# Carte-Principale.net
KiCad netlist of a schematic drawn in EAGLE
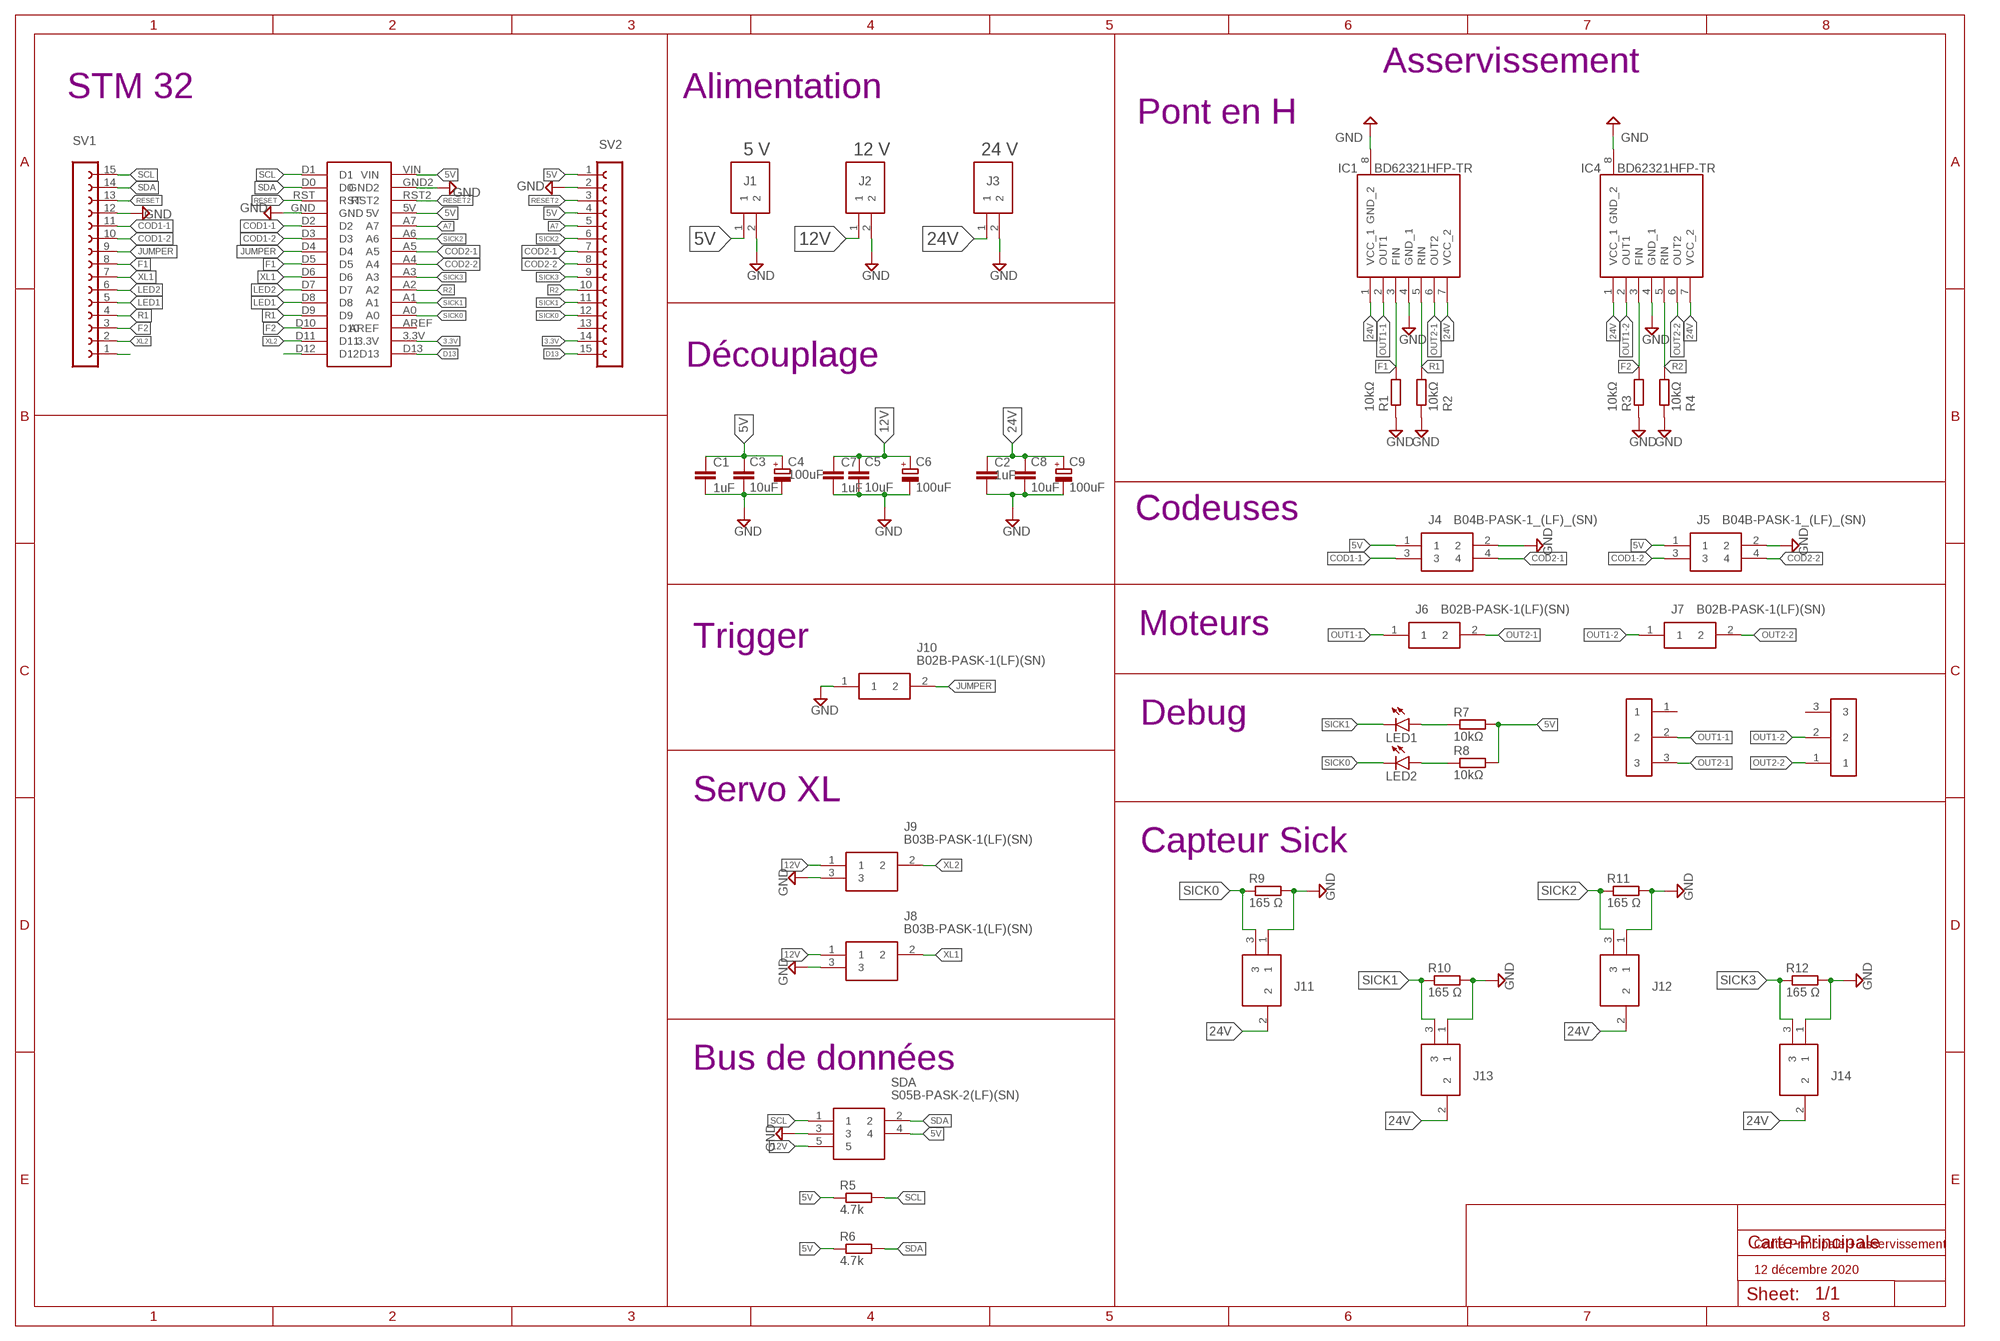
[diagram p0: schematic, sheet 1]

(export (version "E")
  (design (tool "Eeschema 10.0.6"))
  (components
    (comp (ref "C1")
      (value "1uF")
      (footprint "eagle-import:C0805")
      (libsource (lib "eagle-import") (part "C-EUC0805"))
    )
    (comp (ref "C2")
      (value "1uF")
      (footprint "eagle-import:C0805")
      (libsource (lib "eagle-import") (part "C-EUC0805"))
    )
    (comp (ref "C3")
      (value "10uF")
      (footprint "eagle-import:C0805")
      (libsource (lib "eagle-import") (part "C-EUC0805"))
    )
    (comp (ref "C4")
      (value "100uF")
      (footprint "eagle-import:153CLV-0605")
      (libsource (lib "eagle-import") (part "CPOL-EU153CLV-0605"))
    )
    (comp (ref "C5")
      (value "10uF")
      (footprint "eagle-import:C0805")
      (libsource (lib "eagle-import") (part "C-EUC0805"))
    )
    (comp (ref "C6")
      (value "100uF")
      (footprint "eagle-import:153CLV-0605")
      (libsource (lib "eagle-import") (part "CPOL-EU153CLV-0605"))
    )
    (comp (ref "C7")
      (value "1uF")
      (footprint "eagle-import:C0805")
      (libsource (lib "eagle-import") (part "C-EUC0805"))
    )
    (comp (ref "C8")
      (value "10uF")
      (footprint "eagle-import:C0805")
      (libsource (lib "eagle-import") (part "C-EUC0805"))
    )
    (comp (ref "C9")
      (value "100uF")
      (footprint "eagle-import:153CLV-0605")
      (libsource (lib "eagle-import") (part "CPOL-EU153CLV-0605"))
    )
    (comp (ref "IC1")
      (value "BD62321HFP-TR")
      (footprint "eagle-import:HRP7")
      (fields (field (name "MOUSER_PART_NUMBER") "755-BD62321HFP-TR"))
      (libsource (lib "eagle-import") (part "BD62321HFP-TR"))
    )
    (comp (ref "IC4")
      (value "BD62321HFP-TR")
      (footprint "eagle-import:HRP7")
      (fields (field (name "MOUSER_PART_NUMBER") "755-BD62321HFP-TR"))
      (libsource (lib "eagle-import") (part "BD62321HFP-TR"))
    )
    (comp (ref "J1")
      (value "B2P-VH(LF)(SN)")
      (footprint "eagle-import:SHDR2W114P0X396_1X2_786X850X94")
      (fields (field (name "RS_PART_NUMBER") "8201147P"))
      (libsource (lib "eagle-import") (part "B2P-VH(LF)(SN)"))
    )
    (comp (ref "J2")
      (value "B2P-VH(LF)(SN)")
      (footprint "eagle-import:SHDR2W114P0X396_1X2_786X850X94")
      (fields (field (name "RS_PART_NUMBER") "8201147P"))
      (libsource (lib "eagle-import") (part "B2P-VH(LF)(SN)"))
    )
    (comp (ref "J3")
      (value "B2P-VH(LF)(SN)")
      (footprint "eagle-import:SHDR2W114P0X396_1X2_786X850X94")
      (fields (field (name "RS_PART_NUMBER") "8201147P"))
      (libsource (lib "eagle-import") (part "B2P-VH(LF)(SN)"))
    )
    (comp (ref "J4")
      (value "B04B-PASK-1_(LF)_(SN)")
      (footprint "eagle-import:B04B-PASK-1")
      (fields
        (field (name "MANUFACTURER_PART_NUMBER") "B04B-PASK-1 (LF) (SN)")
        (field (name "RS_PART_NUMBER") "5128608P")
      )
      (libsource (lib "eagle-import") (part "B04B-PASK-1_(LF)_(SN)"))
    )
    (comp (ref "J5")
      (value "B04B-PASK-1_(LF)_(SN)")
      (footprint "eagle-import:B04B-PASK-1")
      (fields
        (field (name "MANUFACTURER_PART_NUMBER") "B04B-PASK-1 (LF) (SN)")
        (field (name "RS_PART_NUMBER") "5128608P")
      )
      (libsource (lib "eagle-import") (part "B04B-PASK-1_(LF)_(SN)"))
    )
    (comp (ref "J6")
      (value "B02B-PASK-1(LF)(SN)")
      (footprint "eagle-import:B02BPASK1LFSN")
      (libsource (lib "eagle-import") (part "B02B-PASK-1(LF)(SN)"))
    )
    (comp (ref "J7")
      (value "B02B-PASK-1(LF)(SN)")
      (footprint "eagle-import:B02BPASK1LFSN")
      (libsource (lib "eagle-import") (part "B02B-PASK-1(LF)(SN)"))
    )
    (comp (ref "J8")
      (value "B03B-PASK-1(LF)(SN)")
      (footprint "eagle-import:B03BPASK1LFSN")
      (libsource (lib "eagle-import") (part "B03B-PASK-1(LF)(SN)"))
    )
    (comp (ref "J9")
      (value "B03B-PASK-1(LF)(SN)")
      (footprint "eagle-import:B03BPASK1LFSN")
      (libsource (lib "eagle-import") (part "B03B-PASK-1(LF)(SN)"))
    )
    (comp (ref "J10")
      (value "B02B-PASK-1(LF)(SN)")
      (footprint "eagle-import:B02BPASK1LFSN")
      (libsource (lib "eagle-import") (part "B02B-PASK-1(LF)(SN)"))
    )
    (comp (ref "J11")
      (value "B03B-PASK-1(LF)(SN)")
      (footprint "eagle-import:B03BPASK1LFSN")
      (libsource (lib "eagle-import") (part "B03B-PASK-1(LF)(SN)"))
    )
    (comp (ref "J12")
      (value "B03B-PASK-1(LF)(SN)")
      (footprint "eagle-import:B03BPASK1LFSN")
      (libsource (lib "eagle-import") (part "B03B-PASK-1(LF)(SN)"))
    )
    (comp (ref "J13")
      (value "B03B-PASK-1(LF)(SN)")
      (footprint "eagle-import:B03BPASK1LFSN")
      (libsource (lib "eagle-import") (part "B03B-PASK-1(LF)(SN)"))
    )
    (comp (ref "J14")
      (value "B03B-PASK-1(LF)(SN)")
      (footprint "eagle-import:B03BPASK1LFSN")
      (libsource (lib "eagle-import") (part "B03B-PASK-1(LF)(SN)"))
    )
    (comp (ref "LED1")
      (value "LEDCHIP-LED0805")
      (footprint "eagle-import:CHIP-LED0805")
      (libsource (lib "eagle-import") (part "LEDCHIP-LED0805"))
    )
    (comp (ref "LED2")
      (value "LEDCHIP-LED0805")
      (footprint "eagle-import:CHIP-LED0805")
      (libsource (lib "eagle-import") (part "LEDCHIP-LED0805"))
    )
    (comp (ref "R1")
      (value "10kΩ")
      (footprint "eagle-import:R0805")
      (libsource (lib "eagle-import") (part "R-EU_R0805"))
    )
    (comp (ref "R2")
      (value "10kΩ")
      (footprint "eagle-import:R0805")
      (libsource (lib "eagle-import") (part "R-EU_R0805"))
    )
    (comp (ref "R3")
      (value "10kΩ")
      (footprint "eagle-import:R0805")
      (libsource (lib "eagle-import") (part "R-EU_R0805"))
    )
    (comp (ref "R4")
      (value "10kΩ")
      (footprint "eagle-import:R0805")
      (libsource (lib "eagle-import") (part "R-EU_R0805"))
    )
    (comp (ref "R5")
      (value "4.7k")
      (footprint "eagle-import:R01005")
      (libsource (lib "eagle-import") (part "R-EU_01005"))
    )
    (comp (ref "R6")
      (value "4.7k")
      (footprint "eagle-import:R01005")
      (libsource (lib "eagle-import") (part "R-EU_01005"))
    )
    (comp (ref "R7")
      (value "10kΩ")
      (footprint "eagle-import:R0805")
      (libsource (lib "eagle-import") (part "R-EU_R0805"))
    )
    (comp (ref "R8")
      (value "10kΩ")
      (footprint "eagle-import:R0805")
      (libsource (lib "eagle-import") (part "R-EU_R0805"))
    )
    (comp (ref "R9")
      (value "165 Ω")
      (footprint "eagle-import:R0805")
      (libsource (lib "eagle-import") (part "R-EU_R0805"))
    )
    (comp (ref "R10")
      (value "165 Ω")
      (footprint "eagle-import:R0805")
      (libsource (lib "eagle-import") (part "R-EU_R0805"))
    )
    (comp (ref "R11")
      (value "165 Ω")
      (footprint "eagle-import:R0805")
      (libsource (lib "eagle-import") (part "R-EU_R0805"))
    )
    (comp (ref "R12")
      (value "165 Ω")
      (footprint "eagle-import:R0805")
      (libsource (lib "eagle-import") (part "R-EU_R0805"))
    )
    (comp (ref "SDA")
      (value "S05B-PASK-2(LF)(SN)")
      (footprint "eagle-import:S05B-PASK-2(LF)(SN)")
      (libsource (lib "eagle-import") (part "S05B-PASK-2(LF)(SN)"))
    )
    (comp (ref "SV1")
      (value "FE15-1")
      (footprint "eagle-import:FE15")
      (libsource (lib "eagle-import") (part "FE15-1"))
    )
    (comp (ref "SV2")
      (value "FE15-1")
      (footprint "eagle-import:FE15")
      (libsource (lib "eagle-import") (part "FE15-1"))
    )
    (comp (ref "U$1")
      (value "STM32-L432KC")
      (footprint "eagle-import:STM32-L432KC")
      (libsource (lib "eagle-import") (part "STM32-L432KC"))
    )
    (comp (ref "U$2")
      (value "HEADER3PIN")
      (footprint "eagle-import:HEADER3PINFOOTPRINT")
      (libsource (lib "eagle-import") (part "HEADER3PIN"))
    )
    (comp (ref "U$3")
      (value "HEADER3PIN")
      (footprint "eagle-import:HEADER3PINFOOTPRINT")
      (libsource (lib "eagle-import") (part "HEADER3PIN"))
    )
  )
  (nets
    (net (code "1") (name "3.3V") (class "Default")
      (node (ref "SV2") (pin "14") (pinfunction "14_14") (pintype "passive"))
      (node (ref "U$1") (pin "3.3V") (pinfunction "3.3V_3.3V") (pintype "bidirectional"))
    )
    (net (code "2") (name "5V") (class "Default")
      (node (ref "C1") (pin "1") (pinfunction "1_1") (pintype "passive"))
      (node (ref "C3") (pin "1") (pinfunction "1_1") (pintype "passive"))
      (node (ref "C4") (pin "+") (pinfunction "+_+") (pintype "passive"))
      (node (ref "J1") (pin "1") (pinfunction "1_1") (pintype "bidirectional"))
      (node (ref "J4") (pin "1") (pinfunction "1_1") (pintype "bidirectional"))
      (node (ref "J5") (pin "1") (pinfunction "1_1") (pintype "bidirectional"))
      (node (ref "R5") (pin "1") (pinfunction "1_1") (pintype "passive"))
      (node (ref "R6") (pin "1") (pinfunction "1_1") (pintype "passive"))
      (node (ref "R7") (pin "2") (pinfunction "2_2") (pintype "passive"))
      (node (ref "R8") (pin "2") (pinfunction "2_2") (pintype "passive"))
      (node (ref "SDA") (pin "4") (pinfunction "4_4") (pintype "bidirectional"))
      (node (ref "SV2") (pin "1") (pinfunction "1_1") (pintype "passive"))
      (node (ref "SV2") (pin "4") (pinfunction "4_4") (pintype "passive"))
      (node (ref "U$1") (pin "5V") (pinfunction "5V_5V") (pintype "bidirectional"))
      (node (ref "U$1") (pin "VIN") (pinfunction "VIN_VIN") (pintype "bidirectional"))
    )
    (net (code "3") (name "12V") (class "Default")
      (node (ref "C5") (pin "1") (pinfunction "1_1") (pintype "passive"))
      (node (ref "C6") (pin "+") (pinfunction "+_+") (pintype "passive"))
      (node (ref "C7") (pin "1") (pinfunction "1_1") (pintype "passive"))
      (node (ref "J2") (pin "1") (pinfunction "1_1") (pintype "bidirectional"))
      (node (ref "J8") (pin "1") (pinfunction "1_1") (pintype "bidirectional"))
      (node (ref "J9") (pin "1") (pinfunction "1_1") (pintype "bidirectional"))
      (node (ref "SDA") (pin "5") (pinfunction "5_5") (pintype "bidirectional"))
    )
    (net (code "4") (name "24V") (class "Default")
      (node (ref "C2") (pin "1") (pinfunction "1_1") (pintype "passive"))
      (node (ref "C8") (pin "1") (pinfunction "1_1") (pintype "passive"))
      (node (ref "C9") (pin "+") (pinfunction "+_+") (pintype "passive"))
      (node (ref "IC1") (pin "1") (pinfunction "VCC_1_1") (pintype "bidirectional"))
      (node (ref "IC1") (pin "7") (pinfunction "VCC_2_7") (pintype "bidirectional"))
      (node (ref "IC4") (pin "1") (pinfunction "VCC_1_1") (pintype "bidirectional"))
      (node (ref "IC4") (pin "7") (pinfunction "VCC_2_7") (pintype "bidirectional"))
      (node (ref "J11") (pin "2") (pinfunction "2_2") (pintype "bidirectional"))
      (node (ref "J12") (pin "2") (pinfunction "2_2") (pintype "bidirectional"))
      (node (ref "J13") (pin "2") (pinfunction "2_2") (pintype "bidirectional"))
      (node (ref "J14") (pin "2") (pinfunction "2_2") (pintype "bidirectional"))
      (node (ref "J3") (pin "1") (pinfunction "1_1") (pintype "bidirectional"))
    )
    (net (code "5") (name "A7") (class "Default")
      (node (ref "SV2") (pin "5") (pinfunction "5_5") (pintype "passive"))
      (node (ref "U$1") (pin "A7") (pinfunction "A7_A7") (pintype "bidirectional"))
    )
    (net (code "6") (name "COD1-1") (class "Default")
      (node (ref "J4") (pin "3") (pinfunction "3_3") (pintype "bidirectional"))
      (node (ref "SV1") (pin "11") (pinfunction "11_11") (pintype "passive"))
      (node (ref "U$1") (pin "D2") (pinfunction "D2_D2") (pintype "bidirectional"))
    )
    (net (code "7") (name "COD1-2") (class "Default")
      (node (ref "J5") (pin "3") (pinfunction "3_3") (pintype "bidirectional"))
      (node (ref "SV1") (pin "10") (pinfunction "10_10") (pintype "passive"))
      (node (ref "U$1") (pin "D3") (pinfunction "D3_D3") (pintype "bidirectional"))
    )
    (net (code "8") (name "COD2-1") (class "Default")
      (node (ref "J4") (pin "4") (pinfunction "4_4") (pintype "bidirectional"))
      (node (ref "SV2") (pin "7") (pinfunction "7_7") (pintype "passive"))
      (node (ref "U$1") (pin "A5") (pinfunction "A5_A5") (pintype "bidirectional"))
    )
    (net (code "9") (name "COD2-2") (class "Default")
      (node (ref "J5") (pin "4") (pinfunction "4_4") (pintype "bidirectional"))
      (node (ref "SV2") (pin "8") (pinfunction "8_8") (pintype "passive"))
      (node (ref "U$1") (pin "A4") (pinfunction "A4_A4") (pintype "bidirectional"))
    )
    (net (code "10") (name "D13") (class "Default")
      (node (ref "SV2") (pin "15") (pinfunction "15_15") (pintype "passive"))
      (node (ref "U$1") (pin "D13") (pinfunction "D13_D13") (pintype "bidirectional"))
    )
    (net (code "11") (name "F1") (class "Default")
      (node (ref "IC1") (pin "3") (pinfunction "FIN_3") (pintype "bidirectional"))
      (node (ref "R1") (pin "2") (pinfunction "2_2") (pintype "passive"))
      (node (ref "SV1") (pin "8") (pinfunction "8_8") (pintype "passive"))
      (node (ref "U$1") (pin "D5") (pinfunction "D5_D5") (pintype "bidirectional"))
    )
    (net (code "12") (name "F2") (class "Default")
      (node (ref "IC4") (pin "3") (pinfunction "FIN_3") (pintype "bidirectional"))
      (node (ref "R3") (pin "2") (pinfunction "2_2") (pintype "passive"))
      (node (ref "SV1") (pin "3") (pinfunction "3_3") (pintype "passive"))
      (node (ref "U$1") (pin "D10") (pinfunction "D10_D10") (pintype "bidirectional"))
    )
    (net (code "13") (name "GND") (class "Default")
      (node (ref "C1") (pin "2") (pinfunction "2_2") (pintype "passive"))
      (node (ref "C2") (pin "2") (pinfunction "2_2") (pintype "passive"))
      (node (ref "C3") (pin "2") (pinfunction "2_2") (pintype "passive"))
      (node (ref "C4") (pin "-") (pinfunction "-_-") (pintype "passive"))
      (node (ref "C5") (pin "2") (pinfunction "2_2") (pintype "passive"))
      (node (ref "C6") (pin "-") (pinfunction "-_-") (pintype "passive"))
      (node (ref "C7") (pin "2") (pinfunction "2_2") (pintype "passive"))
      (node (ref "C8") (pin "2") (pinfunction "2_2") (pintype "passive"))
      (node (ref "C9") (pin "-") (pinfunction "-_-") (pintype "passive"))
      (node (ref "IC1") (pin "4") (pinfunction "GND_1_4") (pintype "bidirectional"))
      (node (ref "IC1") (pin "8") (pinfunction "GND_2_8") (pintype "bidirectional"))
      (node (ref "IC4") (pin "4") (pinfunction "GND_1_4") (pintype "bidirectional"))
      (node (ref "IC4") (pin "8") (pinfunction "GND_2_8") (pintype "bidirectional"))
      (node (ref "J1") (pin "2") (pinfunction "2_2") (pintype "bidirectional"))
      (node (ref "J10") (pin "1") (pinfunction "1_1") (pintype "bidirectional"))
      (node (ref "J11") (pin "1") (pinfunction "1_1") (pintype "bidirectional"))
      (node (ref "J12") (pin "1") (pinfunction "1_1") (pintype "bidirectional"))
      (node (ref "J13") (pin "1") (pinfunction "1_1") (pintype "bidirectional"))
      (node (ref "J14") (pin "1") (pinfunction "1_1") (pintype "bidirectional"))
      (node (ref "J2") (pin "2") (pinfunction "2_2") (pintype "bidirectional"))
      (node (ref "J3") (pin "2") (pinfunction "2_2") (pintype "bidirectional"))
      (node (ref "J4") (pin "2") (pinfunction "2_2") (pintype "bidirectional"))
      (node (ref "J5") (pin "2") (pinfunction "2_2") (pintype "bidirectional"))
      (node (ref "J8") (pin "3") (pinfunction "3_3") (pintype "bidirectional"))
      (node (ref "J9") (pin "3") (pinfunction "3_3") (pintype "bidirectional"))
      (node (ref "R1") (pin "1") (pinfunction "1_1") (pintype "passive"))
      (node (ref "R10") (pin "2") (pinfunction "2_2") (pintype "passive"))
      (node (ref "R11") (pin "2") (pinfunction "2_2") (pintype "passive"))
      (node (ref "R12") (pin "2") (pinfunction "2_2") (pintype "passive"))
      (node (ref "R2") (pin "1") (pinfunction "1_1") (pintype "passive"))
      (node (ref "R3") (pin "1") (pinfunction "1_1") (pintype "passive"))
      (node (ref "R4") (pin "1") (pinfunction "1_1") (pintype "passive"))
      (node (ref "R9") (pin "2") (pinfunction "2_2") (pintype "passive"))
      (node (ref "SDA") (pin "3") (pinfunction "3_3") (pintype "bidirectional"))
      (node (ref "SV1") (pin "12") (pinfunction "12_12") (pintype "passive"))
      (node (ref "SV2") (pin "2") (pinfunction "2_2") (pintype "passive"))
      (node (ref "U$1") (pin "GND") (pinfunction "GND_GND") (pintype "bidirectional"))
      (node (ref "U$1") (pin "GND2") (pinfunction "GND2_GND2") (pintype "bidirectional"))
    )
    (net (code "14") (name "JUMPER") (class "Default")
      (node (ref "J10") (pin "2") (pinfunction "2_2") (pintype "bidirectional"))
      (node (ref "SV1") (pin "9") (pinfunction "9_9") (pintype "passive"))
      (node (ref "U$1") (pin "D4") (pinfunction "D4_D4") (pintype "bidirectional"))
    )
    (net (code "15") (name "LED1") (class "Default")
      (node (ref "SV1") (pin "5") (pinfunction "5_5") (pintype "passive"))
      (node (ref "U$1") (pin "D8") (pinfunction "D8_D8") (pintype "bidirectional"))
    )
    (net (code "16") (name "LED2") (class "Default")
      (node (ref "SV1") (pin "6") (pinfunction "6_6") (pintype "passive"))
      (node (ref "U$1") (pin "D7") (pinfunction "D7_D7") (pintype "bidirectional"))
    )
    (net (code "17") (name "Net-(LED1-PadA)") (class "Default")
      (node (ref "LED1") (pin "A") (pinfunction "A_A") (pintype "passive"))
      (node (ref "R7") (pin "1") (pinfunction "1_1") (pintype "passive"))
    )
    (net (code "18") (name "Net-(LED2-PadA)") (class "Default")
      (node (ref "LED2") (pin "A") (pinfunction "A_A") (pintype "passive"))
      (node (ref "R8") (pin "1") (pinfunction "1_1") (pintype "passive"))
    )
    (net (code "19") (name "OUT1-1") (class "Default")
      (node (ref "IC1") (pin "2") (pinfunction "OUT1_2") (pintype "bidirectional"))
      (node (ref "J6") (pin "1") (pinfunction "1_1") (pintype "bidirectional"))
      (node (ref "U$2") (pin "2") (pinfunction "2_2") (pintype "bidirectional"))
    )
    (net (code "20") (name "OUT1-2") (class "Default")
      (node (ref "IC4") (pin "2") (pinfunction "OUT1_2") (pintype "bidirectional"))
      (node (ref "J7") (pin "1") (pinfunction "1_1") (pintype "bidirectional"))
      (node (ref "U$3") (pin "2") (pinfunction "2_2") (pintype "bidirectional"))
    )
    (net (code "21") (name "OUT2-1") (class "Default")
      (node (ref "IC1") (pin "6") (pinfunction "OUT2_6") (pintype "bidirectional"))
      (node (ref "J6") (pin "2") (pinfunction "2_2") (pintype "bidirectional"))
      (node (ref "U$2") (pin "3") (pinfunction "3_3") (pintype "bidirectional"))
    )
    (net (code "22") (name "OUT2-2") (class "Default")
      (node (ref "IC4") (pin "6") (pinfunction "OUT2_6") (pintype "bidirectional"))
      (node (ref "J7") (pin "2") (pinfunction "2_2") (pintype "bidirectional"))
      (node (ref "U$3") (pin "1") (pinfunction "1_1") (pintype "bidirectional"))
    )
    (net (code "23") (name "R1") (class "Default")
      (node (ref "IC1") (pin "5") (pinfunction "RIN_5") (pintype "bidirectional"))
      (node (ref "R2") (pin "2") (pinfunction "2_2") (pintype "passive"))
      (node (ref "SV1") (pin "4") (pinfunction "4_4") (pintype "passive"))
      (node (ref "U$1") (pin "D9") (pinfunction "D9_D9") (pintype "bidirectional"))
    )
    (net (code "24") (name "R2") (class "Default")
      (node (ref "IC4") (pin "5") (pinfunction "RIN_5") (pintype "bidirectional"))
      (node (ref "R4") (pin "2") (pinfunction "2_2") (pintype "passive"))
      (node (ref "SV2") (pin "10") (pinfunction "10_10") (pintype "passive"))
      (node (ref "U$1") (pin "A2") (pinfunction "A2_A2") (pintype "bidirectional"))
    )
    (net (code "25") (name "RESET") (class "Default")
      (node (ref "SV1") (pin "13") (pinfunction "13_13") (pintype "passive"))
      (node (ref "U$1") (pin "RST") (pinfunction "RST_RST") (pintype "bidirectional"))
    )
    (net (code "26") (name "RESET2") (class "Default")
      (node (ref "SV2") (pin "3") (pinfunction "3_3") (pintype "passive"))
      (node (ref "U$1") (pin "RST2") (pinfunction "RST2_RST2") (pintype "bidirectional"))
    )
    (net (code "27") (name "SCL") (class "Default")
      (node (ref "R5") (pin "2") (pinfunction "2_2") (pintype "passive"))
      (node (ref "SDA") (pin "1") (pinfunction "1_1") (pintype "bidirectional"))
      (node (ref "SV1") (pin "15") (pinfunction "15_15") (pintype "passive"))
      (node (ref "U$1") (pin "D1") (pinfunction "D1_D1") (pintype "bidirectional"))
    )
    (net (code "28") (name "SDA") (class "Default")
      (node (ref "R6") (pin "2") (pinfunction "2_2") (pintype "passive"))
      (node (ref "SDA") (pin "2") (pinfunction "2_2") (pintype "bidirectional"))
      (node (ref "SV1") (pin "14") (pinfunction "14_14") (pintype "passive"))
      (node (ref "U$1") (pin "D0") (pinfunction "D0_D0") (pintype "bidirectional"))
    )
    (net (code "29") (name "SICK0") (class "Default")
      (node (ref "J11") (pin "3") (pinfunction "3_3") (pintype "bidirectional"))
      (node (ref "LED2") (pin "C") (pinfunction "C_C") (pintype "passive"))
      (node (ref "R9") (pin "1") (pinfunction "1_1") (pintype "passive"))
      (node (ref "SV2") (pin "12") (pinfunction "12_12") (pintype "passive"))
      (node (ref "U$1") (pin "A0") (pinfunction "A0_A0") (pintype "bidirectional"))
    )
    (net (code "30") (name "SICK1") (class "Default")
      (node (ref "J13") (pin "3") (pinfunction "3_3") (pintype "bidirectional"))
      (node (ref "LED1") (pin "C") (pinfunction "C_C") (pintype "passive"))
      (node (ref "R10") (pin "1") (pinfunction "1_1") (pintype "passive"))
      (node (ref "SV2") (pin "11") (pinfunction "11_11") (pintype "passive"))
      (node (ref "U$1") (pin "A1") (pinfunction "A1_A1") (pintype "bidirectional"))
    )
    (net (code "31") (name "SICK2") (class "Default")
      (node (ref "J12") (pin "3") (pinfunction "3_3") (pintype "bidirectional"))
      (node (ref "R11") (pin "1") (pinfunction "1_1") (pintype "passive"))
      (node (ref "SV2") (pin "6") (pinfunction "6_6") (pintype "passive"))
      (node (ref "U$1") (pin "A6") (pinfunction "A6_A6") (pintype "bidirectional"))
    )
    (net (code "32") (name "SICK3") (class "Default")
      (node (ref "J14") (pin "3") (pinfunction "3_3") (pintype "bidirectional"))
      (node (ref "R12") (pin "1") (pinfunction "1_1") (pintype "passive"))
      (node (ref "SV2") (pin "9") (pinfunction "9_9") (pintype "passive"))
      (node (ref "U$1") (pin "A3") (pinfunction "A3_A3") (pintype "bidirectional"))
    )
    (net (code "33") (name "XL1") (class "Default")
      (node (ref "J8") (pin "2") (pinfunction "2_2") (pintype "bidirectional"))
      (node (ref "SV1") (pin "7") (pinfunction "7_7") (pintype "passive"))
      (node (ref "U$1") (pin "D6") (pinfunction "D6_D6") (pintype "bidirectional"))
    )
    (net (code "34") (name "XL2") (class "Default")
      (node (ref "J9") (pin "2") (pinfunction "2_2") (pintype "bidirectional"))
      (node (ref "SV1") (pin "2") (pinfunction "2_2") (pintype "passive"))
      (node (ref "U$1") (pin "D11") (pinfunction "D11_D11") (pintype "bidirectional"))
    )
    (net (code "35") (name "unconnected-(SV1-Pad1)") (class "Default")
      (node (ref "SV1") (pin "1") (pinfunction "1_1") (pintype "passive"))
    )
    (net (code "36") (name "unconnected-(SV2-Pad13)") (class "Default")
      (node (ref "SV2") (pin "13") (pinfunction "13_13") (pintype "passive"))
    )
    (net (code "37") (name "unconnected-(U$1-PadAREF)") (class "Default")
      (node (ref "U$1") (pin "AREF") (pinfunction "AREF_AREF") (pintype "bidirectional"))
    )
    (net (code "38") (name "unconnected-(U$1-PadD12)") (class "Default")
      (node (ref "U$1") (pin "D12") (pinfunction "D12_D12") (pintype "bidirectional"))
    )
    (net (code "39") (name "unconnected-(U$2-Pad1)") (class "Default")
      (node (ref "U$2") (pin "1") (pinfunction "1_1") (pintype "bidirectional"))
    )
    (net (code "40") (name "unconnected-(U$3-Pad3)") (class "Default")
      (node (ref "U$3") (pin "3") (pinfunction "3_3") (pintype "bidirectional"))
    )
  )
)
